# 130818_I_T_V_AriloRX_0_0.net
KiCad netlist of a schematic drawn in EAGLE
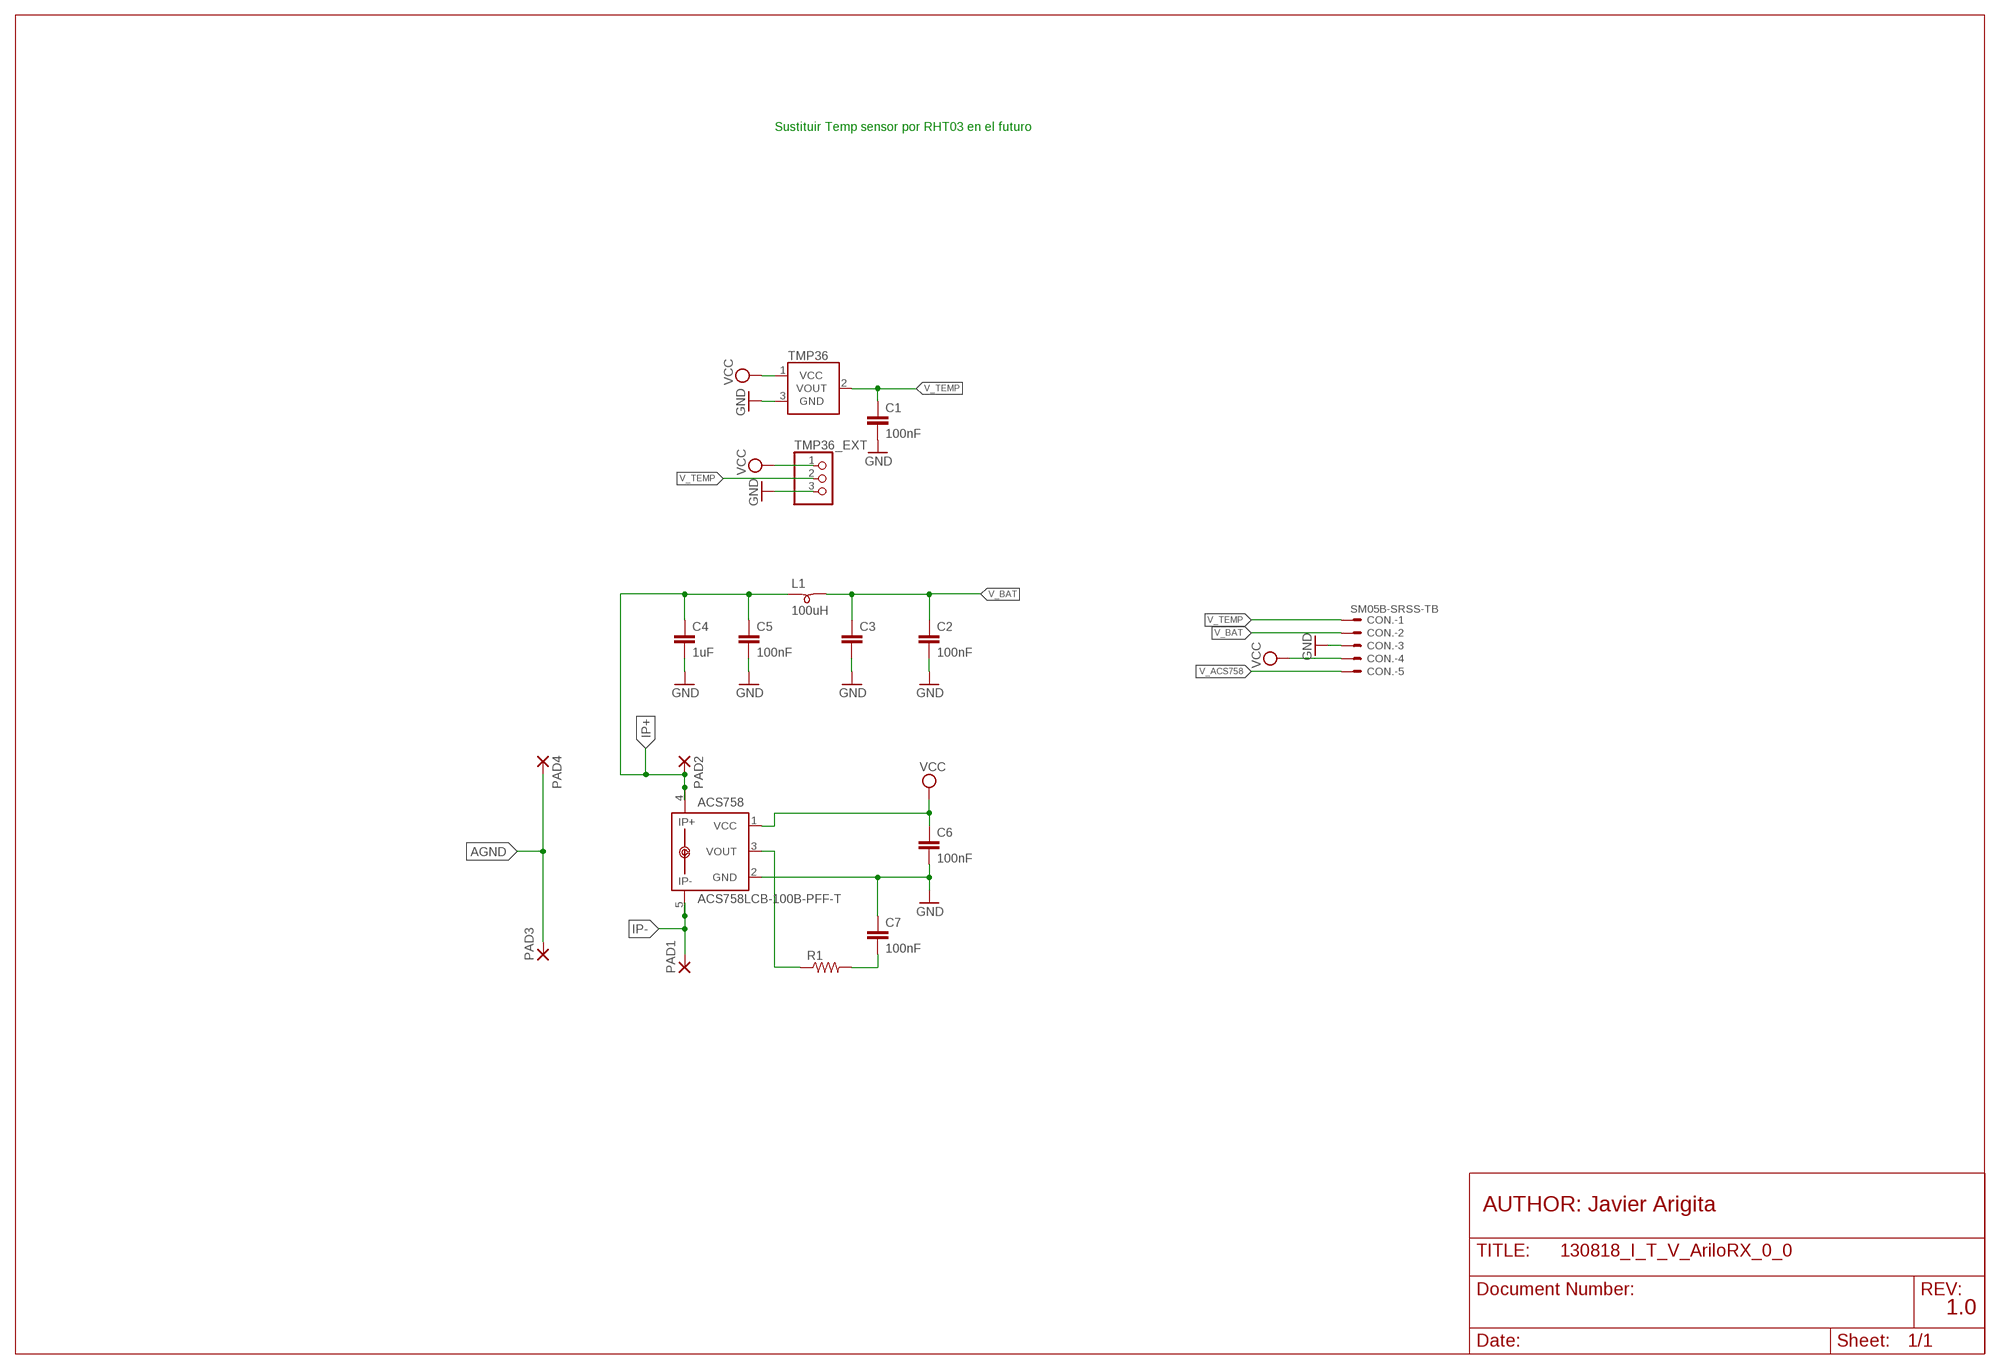
[diagram p0: schematic, sheet 1]

(export (version "E")
  (design (tool "Eeschema 10.0.6"))
  (components
    (comp (ref "ACS758")
      (value "ACS758LCB-100B-PFF-T")
      (footprint "eagle-import:CB-PFF")
      (libsource (lib "eagle-import") (part "ACS758LCB-100B-PFF-T"))
    )
    (comp (ref "C1")
      (value "100nF")
      (footprint "eagle-import:C0805")
      (libsource (lib "eagle-import") (part "C-EUC0805"))
    )
    (comp (ref "C2")
      (value "100nF")
      (footprint "eagle-import:C0805")
      (libsource (lib "eagle-import") (part "C-EUC0805"))
    )
    (comp (ref "C3")
      (value "C-EUC3216")
      (footprint "eagle-import:C3216")
      (libsource (lib "eagle-import") (part "C-EUC3216"))
    )
    (comp (ref "C4")
      (value "1uF")
      (footprint "eagle-import:C3216")
      (libsource (lib "eagle-import") (part "C-EUC3216"))
    )
    (comp (ref "C5")
      (value "100nF")
      (footprint "eagle-import:C0805")
      (libsource (lib "eagle-import") (part "C-EUC0805"))
    )
    (comp (ref "C6")
      (value "100nF")
      (footprint "eagle-import:C0805")
      (libsource (lib "eagle-import") (part "C-EUC0805"))
    )
    (comp (ref "C7")
      (value "100nF")
      (footprint "eagle-import:C0805")
      (libsource (lib "eagle-import") (part "C-EUC0805"))
    )
    (comp (ref "CON.")
      (value "SM05B-SRSS-TB")
      (footprint "eagle-import:SM05B-SRSS-TB")
      (libsource (lib "eagle-import") (part "?M05B-SRSS-TBS"))
    )
    (comp (ref "L1")
      (value "100uH")
      (footprint "eagle-import:SM-B5")
      (libsource (lib "eagle-import") (part "SM-B5"))
    )
    (comp (ref "PAD1")
      (value "SMD5")
      (footprint "eagle-import:SMD2,54-5,08")
      (libsource (lib "eagle-import") (part "SMD5"))
    )
    (comp (ref "PAD2")
      (value "SMD5")
      (footprint "eagle-import:SMD2,54-5,08")
      (libsource (lib "eagle-import") (part "SMD5"))
    )
    (comp (ref "PAD3")
      (value "SMD5")
      (footprint "eagle-import:SMD2,54-5,08")
      (libsource (lib "eagle-import") (part "SMD5"))
    )
    (comp (ref "PAD4")
      (value "SMD5")
      (footprint "eagle-import:SMD2,54-5,08")
      (libsource (lib "eagle-import") (part "SMD5"))
    )
    (comp (ref "R1")
      (value "RESISTOR0805")
      (footprint "eagle-import:R0805")
      (libsource (lib "eagle-import") (part "RESISTOR0805"))
    )
    (comp (ref "TMP36")
      (value "TMP36GT9")
      (footprint "eagle-import:TO-92")
      (libsource (lib "eagle-import") (part "TMP36GT9"))
    )
    (comp (ref "TMP36_EXT")
      (value "PINHD-1X3")
      (footprint "eagle-import:1X03")
      (libsource (lib "eagle-import") (part "PINHD-1X3"))
    )
  )
  (nets
    (net (code "1") (name "AGND") (class "Default")
      (node (ref "PAD3") (pin "1") (pinfunction "P_1") (pintype "passive"))
      (node (ref "PAD4") (pin "1") (pinfunction "P_1") (pintype "passive"))
    )
    (net (code "2") (name "GND") (class "Default")
      (node (ref "ACS758") (pin "2") (pinfunction "GND_2") (pintype "power_in"))
      (node (ref "C1") (pin "2") (pinfunction "2_2") (pintype "passive"))
      (node (ref "C2") (pin "2") (pinfunction "2_2") (pintype "passive"))
      (node (ref "C3") (pin "2") (pinfunction "2_2") (pintype "passive"))
      (node (ref "C4") (pin "2") (pinfunction "2_2") (pintype "passive"))
      (node (ref "C5") (pin "2") (pinfunction "2_2") (pintype "passive"))
      (node (ref "C6") (pin "2") (pinfunction "2_2") (pintype "passive"))
      (node (ref "C7") (pin "1") (pinfunction "1_1") (pintype "passive"))
      (node (ref "CON.") (pin "3") (pinfunction "S_3") (pintype "passive"))
      (node (ref "TMP36") (pin "3") (pinfunction "GND_3") (pintype "bidirectional"))
      (node (ref "TMP36_EXT") (pin "3") (pinfunction "3_3") (pintype "passive"))
    )
    (net (code "3") (name "IP+") (class "Default")
      (node (ref "ACS758") (pin "4") (pinfunction "IP+_4") (pintype "passive"))
      (node (ref "ACS758") (pin "IP+1") (pinfunction "IP+1_IP+1") (pintype "input"))
      (node (ref "C4") (pin "1") (pinfunction "1_1") (pintype "passive"))
      (node (ref "C5") (pin "1") (pinfunction "1_1") (pintype "passive"))
      (node (ref "L1") (pin "1") (pinfunction "1_1") (pintype "passive"))
      (node (ref "PAD2") (pin "1") (pinfunction "P_1") (pintype "passive"))
    )
    (net (code "4") (name "IP-") (class "Default")
      (node (ref "ACS758") (pin "5") (pinfunction "IP-_5") (pintype "passive"))
      (node (ref "ACS758") (pin "IP-1") (pinfunction "IP-1_IP-1") (pintype "input"))
      (node (ref "PAD1") (pin "1") (pinfunction "P_1") (pintype "passive"))
    )
    (net (code "5") (name "Net-(ACS758-VOUT)") (class "Default")
      (node (ref "ACS758") (pin "3") (pinfunction "VOUT_3") (pintype "output"))
      (node (ref "R1") (pin "1") (pinfunction "1_1") (pintype "passive"))
    )
    (net (code "6") (name "Net-(C7-Pad2)") (class "Default")
      (node (ref "C7") (pin "2") (pinfunction "2_2") (pintype "passive"))
      (node (ref "R1") (pin "2") (pinfunction "2_2") (pintype "passive"))
    )
    (net (code "7") (name "VCC") (class "Default")
      (node (ref "ACS758") (pin "1") (pinfunction "VCC_1") (pintype "power_in"))
      (node (ref "C6") (pin "1") (pinfunction "1_1") (pintype "passive"))
      (node (ref "CON.") (pin "4") (pinfunction "S_4") (pintype "passive"))
      (node (ref "TMP36") (pin "1") (pinfunction "VCC_1") (pintype "bidirectional"))
      (node (ref "TMP36_EXT") (pin "1") (pinfunction "1_1") (pintype "passive"))
    )
    (net (code "8") (name "V_ACS758") (class "Default")
      (node (ref "CON.") (pin "5") (pinfunction "S_5") (pintype "passive"))
    )
    (net (code "9") (name "V_BAT") (class "Default")
      (node (ref "C2") (pin "1") (pinfunction "1_1") (pintype "passive"))
      (node (ref "C3") (pin "1") (pinfunction "1_1") (pintype "passive"))
      (node (ref "CON.") (pin "2") (pinfunction "S_2") (pintype "passive"))
      (node (ref "L1") (pin "2") (pinfunction "2_2") (pintype "passive"))
    )
    (net (code "10") (name "V_TEMP") (class "Default")
      (node (ref "C1") (pin "1") (pinfunction "1_1") (pintype "passive"))
      (node (ref "CON.") (pin "1") (pinfunction "S_1") (pintype "passive"))
      (node (ref "TMP36") (pin "2") (pinfunction "VOUT_2") (pintype "bidirectional"))
      (node (ref "TMP36_EXT") (pin "2") (pinfunction "2_2") (pintype "passive"))
    )
  )
)
